# AMP_MAIN_REV1_0.net
KiCad netlist of a schematic drawn in Altium Designer
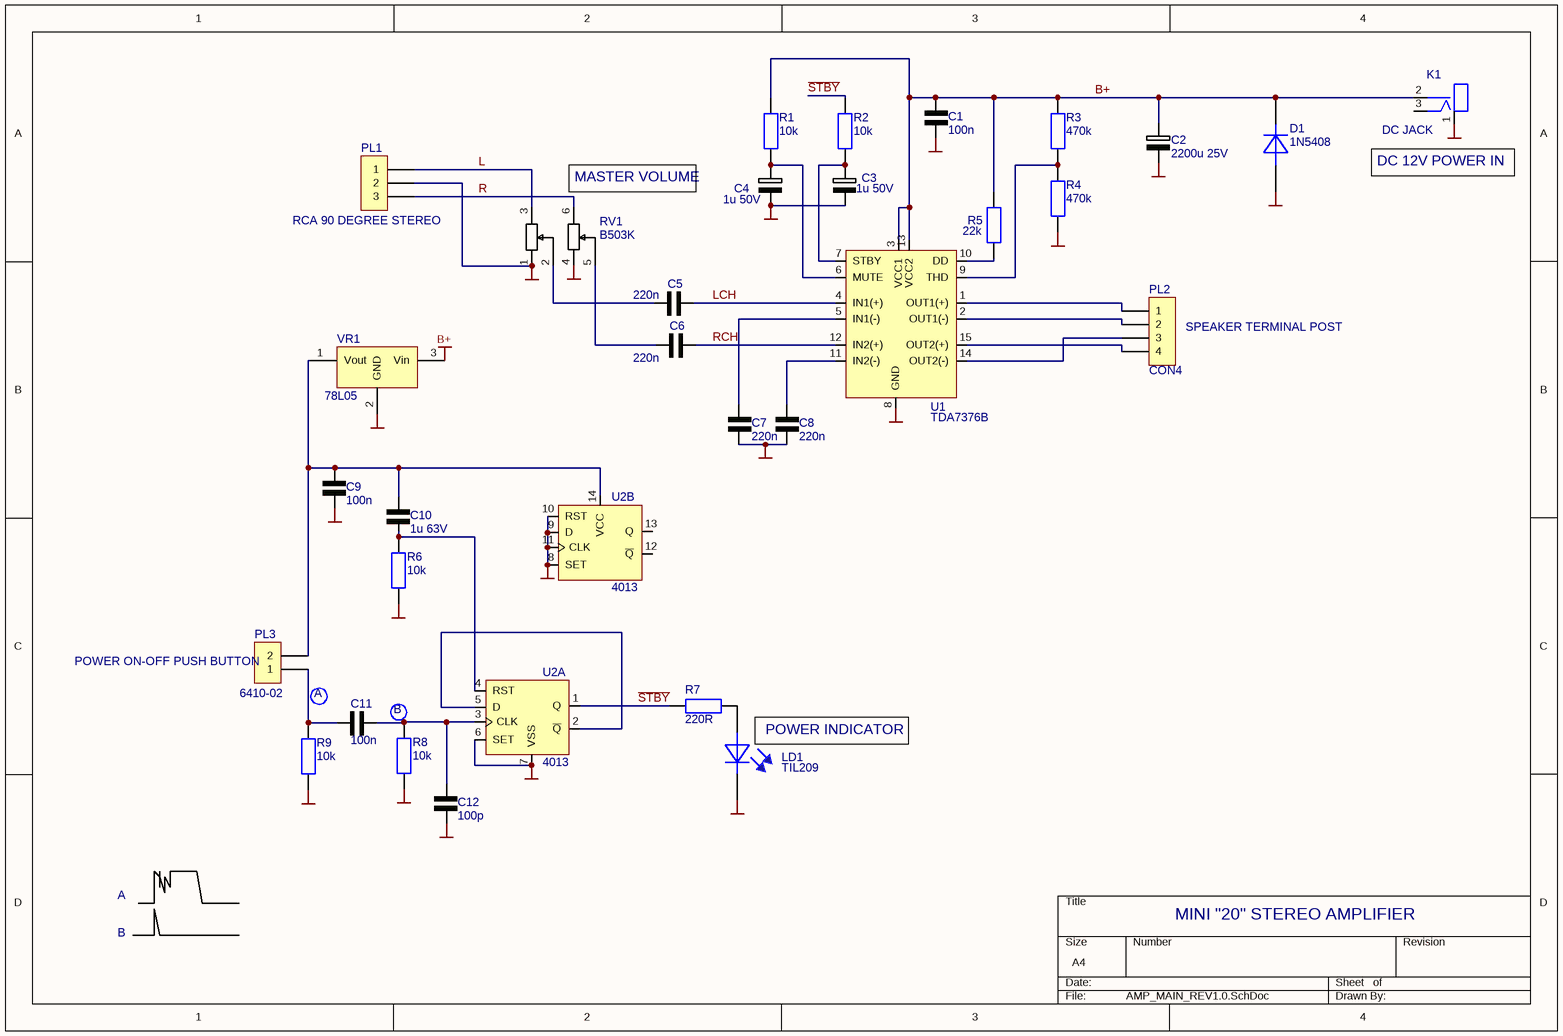
[diagram p0: AMP_MAIN_REV1.0.SchDoc]

(export (version "E")
  (design (tool "Eeschema 10.0.6"))
  (components
    (comp (ref "C1")
      (value "100n")
      (footprint "CAP200")
      (libsource (lib "SCHEMATIC SYMBOLS") (part "CAPACITOR"))
    )
    (comp (ref "C2")
      (value "2200u 25V")
      (footprint "CAP RADIAL 13/26")
      (libsource (lib "SCHEMATIC SYMBOLS") (part "POL_CAP"))
    )
    (comp (ref "C3")
      (value "1u 50V")
      (footprint "CAP PF 5.08/6.5")
      (libsource (lib "SCHEMATIC SYMBOLS") (part "POL_CAP"))
    )
    (comp (ref "C4")
      (value "1u 50V")
      (footprint "CAP PF 5.08/6.5")
      (libsource (lib "SCHEMATIC SYMBOLS") (part "POL_CAP"))
    )
    (comp (ref "C5")
      (value "220n")
      (footprint "CAP POLY 5.08/7.5/2.5")
      (libsource (lib "SCHEMATIC SYMBOLS") (part "CAPACITOR"))
    )
    (comp (ref "C6")
      (value "220n")
      (footprint "CAP POLY 5.08/7.5/2.5")
      (libsource (lib "SCHEMATIC SYMBOLS") (part "CAPACITOR"))
    )
    (comp (ref "C7")
      (value "220n")
      (footprint "CAP POLY 5.08/7.5/2.5")
      (libsource (lib "SCHEMATIC SYMBOLS") (part "CAPACITOR"))
    )
    (comp (ref "C8")
      (value "220n")
      (footprint "CAP POLY 5.08/7.5/2.5")
      (libsource (lib "SCHEMATIC SYMBOLS") (part "CAPACITOR"))
    )
    (comp (ref "C9")
      (value "100n")
      (footprint "CAP200")
      (libsource (lib "SCHEMATIC SYMBOLS") (part "CAPACITOR"))
    )
    (comp (ref "C10")
      (value "1u 63V")
      (footprint "WIMA MKS 2")
      (libsource (lib "SCHEMATIC SYMBOLS") (part "CAPACITOR"))
    )
    (comp (ref "C11")
      (value "100n")
      (footprint "CAP200")
      (libsource (lib "SCHEMATIC SYMBOLS") (part "CAPACITOR"))
    )
    (comp (ref "C12")
      (value "100p")
      (footprint "CAP200")
      (libsource (lib "SCHEMATIC SYMBOLS") (part "CAPACITOR"))
    )
    (comp (ref "D1")
      (value "1N5408")
      (footprint "DIODE 1N5408")
      (libsource (lib "SCHEMATIC SYMBOLS") (part "STD_DIODE"))
    )
    (comp (ref "K1")
      (value "DC JACK")
      (footprint "DC JACK")
      (libsource (lib "SCHEMATIC SYMBOLS") (part "DC JACK"))
    )
    (comp (ref "LD1")
      (value "TIL209")
      (footprint "LED_RA_5MM")
      (libsource (lib "SCHEMATIC SYMBOLS") (part "STD_LED"))
    )
    (comp (ref "PL1")
      (value "RCA 90 DEGREE STEREO")
      (footprint "RCA_STEREO_PCB_VERTICAL")
      (description "3 Way Connector")
      (libsource (lib "SCHEMATIC SYMBOLS") (part "CON3"))
    )
    (comp (ref "PL2")
      (value "CON4")
      (footprint "SPEAKER_TERMINAL_PCB")
      (description "4 Way Connector")
      (libsource (lib "SCHEMATIC SYMBOLS") (part "CON4"))
    )
    (comp (ref "PL3")
      (value "6410-02")
      (footprint "CON MOLEX 6410 2 WAY")
      (description "2 Way connector")
      (libsource (lib "SCHEMATIC SYMBOLS") (part "CON2"))
    )
    (comp (ref "R1")
      (value "10k")
      (footprint "RES 1/4W H")
      (libsource (lib "SCHEMATIC SYMBOLS") (part "RES"))
    )
    (comp (ref "R2")
      (value "10k")
      (footprint "RES 1/4W H")
      (libsource (lib "SCHEMATIC SYMBOLS") (part "RES"))
    )
    (comp (ref "R3")
      (value "470k")
      (footprint "RES 1/4W H")
      (libsource (lib "SCHEMATIC SYMBOLS") (part "RES"))
    )
    (comp (ref "R4")
      (value "470k")
      (footprint "RES 1/4W H")
      (libsource (lib "SCHEMATIC SYMBOLS") (part "RES"))
    )
    (comp (ref "R5")
      (value "22k")
      (footprint "RES 1/4W H")
      (libsource (lib "SCHEMATIC SYMBOLS") (part "RES"))
    )
    (comp (ref "R6")
      (value "10k")
      (footprint "RES 1/4W H")
      (libsource (lib "SCHEMATIC SYMBOLS") (part "RES"))
    )
    (comp (ref "R7")
      (value "220R")
      (footprint "RES 1/4W H")
      (libsource (lib "SCHEMATIC SYMBOLS") (part "RES"))
    )
    (comp (ref "R8")
      (value "10k")
      (footprint "RES 1/4W H")
      (libsource (lib "SCHEMATIC SYMBOLS") (part "RES"))
    )
    (comp (ref "R9")
      (value "10k")
      (footprint "RES 1/4W H")
      (libsource (lib "SCHEMATIC SYMBOLS") (part "RES"))
    )
    (comp (ref "RV1")
      (value "B503K")
      (footprint "ALPS 043R")
      (libsource (lib "SCHEMATIC SYMBOLS") (part "POT DUAL GANGED"))
    )
    (comp (ref "U1")
      (value "TDA7376B")
      (footprint "MULTIWATT15V")
      (description "Stereo 35W Automotive Power Amplifier")
      (libsource (lib "SCHEMATIC SYMBOLS") (part "TDA7376"))
    )
    (comp (ref "U2")
      (value "4013")
      (footprint "DIP 14")
      (description "FLIP-FLOP")
      (libsource (lib "SCHEMATIC SYMBOLS") (part "4013"))
    )
    (comp (ref "VR1")
      (value "78L05")
      (footprint "TO92_REGULATOR")
      (description "Low power fixed voltage regulator")
      (libsource (lib "SCHEMATIC SYMBOLS") (part "REG 78LXX"))
    )
  )
  (nets
    (net (code "1") (name "/L") (class "Default")
      (node (ref "PL1") (pin "1") (pinfunction "1_1") (pintype "passive"))
      (node (ref "RV1") (pin "3") (pinfunction "B_3") (pintype "passive"))
    )
    (net (code "2") (name "/LCH") (class "Default")
      (node (ref "C5") (pin "2") (pinfunction "2_2") (pintype "passive"))
      (node (ref "U1") (pin "4") (pinfunction "IN1(+)_4") (pintype "passive"))
    )
    (net (code "3") (name "/R") (class "Default")
      (node (ref "PL1") (pin "3") (pinfunction "3_3") (pintype "passive"))
      (node (ref "RV1") (pin "6") (pinfunction "B_6") (pintype "passive"))
    )
    (net (code "4") (name "/RCH") (class "Default")
      (node (ref "C6") (pin "2") (pinfunction "2_2") (pintype "passive"))
      (node (ref "U1") (pin "12") (pinfunction "IN2(+)_12") (pintype "passive"))
    )
    (net (code "5") (name "/~{STBY}") (class "Default")
      (node (ref "R2") (pin "2") (pinfunction "2_2") (pintype "passive"))
      (node (ref "R7") (pin "2") (pinfunction "2_2") (pintype "passive"))
      (node (ref "U2") (pin "1") (pinfunction "Q_1") (pintype "passive"))
    )
    (net (code "6") (name "B+") (class "Default")
      (node (ref "C1") (pin "2") (pinfunction "2_2") (pintype "passive"))
      (node (ref "C2") (pin "1") (pinfunction "1_1") (pintype "passive"))
      (node (ref "D1") (pin "2") (pinfunction "K_2") (pintype "passive"))
      (node (ref "K1") (pin "2") (pinfunction "2_2") (pintype "passive"))
      (node (ref "R1") (pin "2") (pinfunction "2_2") (pintype "passive"))
      (node (ref "R3") (pin "2") (pinfunction "2_2") (pintype "passive"))
      (node (ref "R5") (pin "2") (pinfunction "2_2") (pintype "passive"))
      (node (ref "U1") (pin "13") (pinfunction "VCC2_13") (pintype "passive"))
      (node (ref "U1") (pin "3") (pinfunction "VCC1_3") (pintype "passive"))
      (node (ref "VR1") (pin "3") (pinfunction "Vin_3") (pintype "passive"))
    )
    (net (code "7") (name "GND") (class "Default")
      (node (ref "C1") (pin "1") (pinfunction "1_1") (pintype "passive"))
      (node (ref "C12") (pin "2") (pinfunction "2_2") (pintype "passive"))
      (node (ref "C2") (pin "2") (pinfunction "2_2") (pintype "passive"))
      (node (ref "C3") (pin "2") (pinfunction "2_2") (pintype "passive"))
      (node (ref "C4") (pin "2") (pinfunction "2_2") (pintype "passive"))
      (node (ref "C7") (pin "1") (pinfunction "1_1") (pintype "passive"))
      (node (ref "C8") (pin "1") (pinfunction "1_1") (pintype "passive"))
      (node (ref "C9") (pin "2") (pinfunction "2_2") (pintype "passive"))
      (node (ref "D1") (pin "1") (pinfunction "A_1") (pintype "passive"))
      (node (ref "K1") (pin "1") (pinfunction "1_1") (pintype "passive"))
      (node (ref "LD1") (pin "K") (pinfunction "K_K") (pintype "passive"))
      (node (ref "PL1") (pin "2") (pinfunction "2_2") (pintype "passive"))
      (node (ref "R4") (pin "1") (pinfunction "1_1") (pintype "passive"))
      (node (ref "R6") (pin "1") (pinfunction "1_1") (pintype "passive"))
      (node (ref "R8") (pin "1") (pinfunction "1_1") (pintype "passive"))
      (node (ref "R9") (pin "1") (pinfunction "1_1") (pintype "passive"))
      (node (ref "RV1") (pin "1") (pinfunction "A_1") (pintype "passive"))
      (node (ref "RV1") (pin "4") (pinfunction "A_4") (pintype "passive"))
      (node (ref "U1") (pin "8") (pinfunction "GND_8") (pintype "passive"))
      (node (ref "U2") (pin "10") (pinfunction "RST_10") (pintype "passive"))
      (node (ref "U2") (pin "11") (pinfunction "CLK_11") (pintype "passive"))
      (node (ref "U2") (pin "6") (pinfunction "SET_6") (pintype "passive"))
      (node (ref "U2") (pin "7") (pinfunction "VSS_7") (pintype "passive"))
      (node (ref "U2") (pin "8") (pinfunction "SET_8") (pintype "passive"))
      (node (ref "U2") (pin "9") (pinfunction "D_9") (pintype "passive"))
      (node (ref "VR1") (pin "2") (pinfunction "GND_2") (pintype "passive"))
    )
    (net (code "8") (name "Net-(C5-Pad1)") (class "Default")
      (node (ref "C5") (pin "1") (pinfunction "1_1") (pintype "passive"))
      (node (ref "RV1") (pin "2") (pinfunction "W_2") (pintype "passive"))
    )
    (net (code "9") (name "Net-(C6-Pad1)") (class "Default")
      (node (ref "C6") (pin "1") (pinfunction "1_1") (pintype "passive"))
      (node (ref "RV1") (pin "5") (pinfunction "W_5") (pintype "passive"))
    )
    (net (code "10") (name "Net-(C11-Pad1)") (class "Default")
      (node (ref "C11") (pin "1") (pinfunction "1_1") (pintype "passive"))
      (node (ref "PL3") (pin "1") (pinfunction "1_1") (pintype "passive"))
      (node (ref "R9") (pin "2") (pinfunction "2_2") (pintype "passive"))
    )
    (net (code "11") (name "Net-(LD1-PadA)") (class "Default")
      (node (ref "LD1") (pin "A") (pinfunction "A_A") (pintype "passive"))
      (node (ref "R7") (pin "1") (pinfunction "1_1") (pintype "passive"))
    )
    (net (code "12") (name "Net-(U1-DD)") (class "Default")
      (node (ref "R5") (pin "1") (pinfunction "1_1") (pintype "passive"))
      (node (ref "U1") (pin "10") (pinfunction "DD_10") (pintype "passive"))
    )
    (net (code "13") (name "Net-(U1-IN1(-))") (class "Default")
      (node (ref "C7") (pin "2") (pinfunction "2_2") (pintype "passive"))
      (node (ref "U1") (pin "5") (pinfunction "IN1(-)_5") (pintype "passive"))
    )
    (net (code "14") (name "Net-(U1-IN2(-))") (class "Default")
      (node (ref "C8") (pin "2") (pinfunction "2_2") (pintype "passive"))
      (node (ref "U1") (pin "11") (pinfunction "IN2(-)_11") (pintype "passive"))
    )
    (net (code "15") (name "Net-(U1-MUTE)") (class "Default")
      (node (ref "C4") (pin "1") (pinfunction "1_1") (pintype "passive"))
      (node (ref "R1") (pin "1") (pinfunction "1_1") (pintype "passive"))
      (node (ref "U1") (pin "6") (pinfunction "MUTE_6") (pintype "passive"))
    )
    (net (code "16") (name "Net-(U1-OUT1(+))") (class "Default")
      (node (ref "PL2") (pin "1") (pinfunction "1_1") (pintype "passive"))
      (node (ref "U1") (pin "1") (pinfunction "OUT1(+)_1") (pintype "passive"))
    )
    (net (code "17") (name "Net-(U1-OUT1(-))") (class "Default")
      (node (ref "PL2") (pin "2") (pinfunction "2_2") (pintype "passive"))
      (node (ref "U1") (pin "2") (pinfunction "OUT1(-)_2") (pintype "passive"))
    )
    (net (code "18") (name "Net-(U1-OUT2(+))") (class "Default")
      (node (ref "PL2") (pin "4") (pinfunction "4_4") (pintype "passive"))
      (node (ref "U1") (pin "15") (pinfunction "OUT2(+)_15") (pintype "passive"))
    )
    (net (code "19") (name "Net-(U1-OUT2(-))") (class "Default")
      (node (ref "PL2") (pin "3") (pinfunction "3_3") (pintype "passive"))
      (node (ref "U1") (pin "14") (pinfunction "OUT2(-)_14") (pintype "passive"))
    )
    (net (code "20") (name "Net-(U1-STBY)") (class "Default")
      (node (ref "C3") (pin "1") (pinfunction "1_1") (pintype "passive"))
      (node (ref "R2") (pin "1") (pinfunction "1_1") (pintype "passive"))
      (node (ref "U1") (pin "7") (pinfunction "STBY_7") (pintype "passive"))
    )
    (net (code "21") (name "Net-(U1-THD)") (class "Default")
      (node (ref "R3") (pin "1") (pinfunction "1_1") (pintype "passive"))
      (node (ref "R4") (pin "2") (pinfunction "2_2") (pintype "passive"))
      (node (ref "U1") (pin "9") (pinfunction "THD_9") (pintype "passive"))
    )
    (net (code "22") (name "Net-(U2A-CLK)") (class "Default")
      (node (ref "C11") (pin "2") (pinfunction "2_2") (pintype "passive"))
      (node (ref "C12") (pin "1") (pinfunction "1_1") (pintype "passive"))
      (node (ref "R8") (pin "2") (pinfunction "2_2") (pintype "passive"))
      (node (ref "U2") (pin "3") (pinfunction "CLK_3") (pintype "passive"))
    )
    (net (code "23") (name "Net-(U2A-D)") (class "Default")
      (node (ref "U2") (pin "2") (pinfunction "~{Q}_2") (pintype "passive"))
      (node (ref "U2") (pin "5") (pinfunction "D_5") (pintype "passive"))
    )
    (net (code "24") (name "Net-(U2A-RST)") (class "Default")
      (node (ref "C10") (pin "2") (pinfunction "2_2") (pintype "passive"))
      (node (ref "R6") (pin "2") (pinfunction "2_2") (pintype "passive"))
      (node (ref "U2") (pin "4") (pinfunction "RST_4") (pintype "passive"))
    )
    (net (code "25") (name "Net-(U2B-VCC)") (class "Default")
      (node (ref "C10") (pin "1") (pinfunction "1_1") (pintype "passive"))
      (node (ref "C9") (pin "1") (pinfunction "1_1") (pintype "passive"))
      (node (ref "PL3") (pin "2") (pinfunction "2_2") (pintype "passive"))
      (node (ref "U2") (pin "14") (pinfunction "VCC_14") (pintype "passive"))
      (node (ref "VR1") (pin "1") (pinfunction "Vout_1") (pintype "passive"))
    )
    (net (code "26") (name "unconnected-(K1-Pad3)") (class "Default")
      (node (ref "K1") (pin "3") (pinfunction "3_3") (pintype "passive"))
    )
    (net (code "27") (name "unconnected-(U2B-Q-Pad13)") (class "Default")
      (node (ref "U2") (pin "13") (pinfunction "Q_13") (pintype "passive"))
    )
    (net (code "28") (name "unconnected-(U2B-~{Q}-Pad12)") (class "Default")
      (node (ref "U2") (pin "12") (pinfunction "~{Q}_12") (pintype "passive"))
    )
  )
)
